# MLX90614-IR_v4.net
KiCad netlist of a schematic drawn in EAGLE
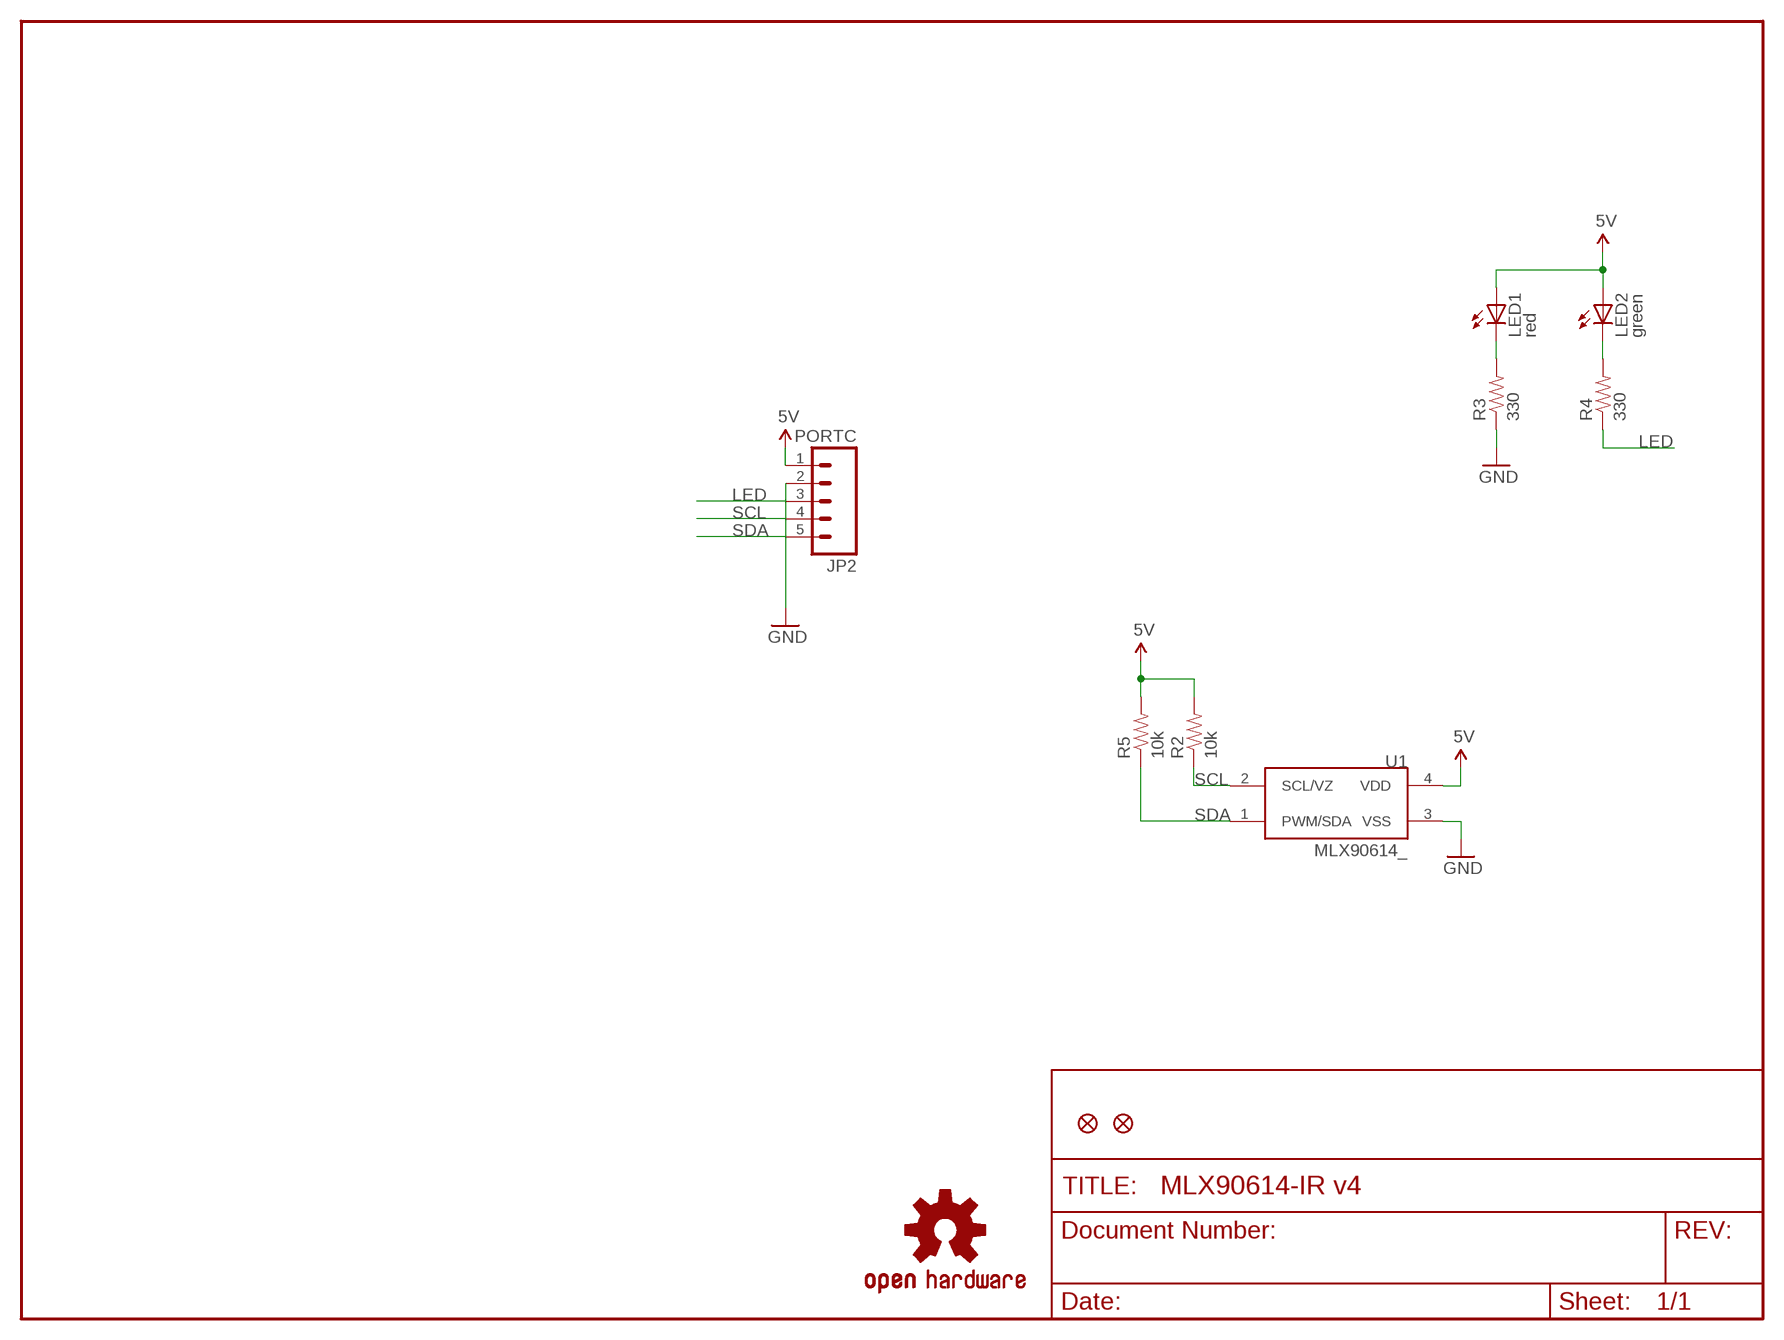
[diagram p0: schematic, sheet 1]

(export (version "E")
  (design (tool "Eeschema 10.0.6"))
  (components
    (comp (ref "JP2")
      (value "PORTC")
      (footprint "eagle-import:1X05")
      (libsource (lib "eagle-import") (part "M05PTH"))
    )
    (comp (ref "JP3")
      (value "FIDUCIAL1X2.5")
      (footprint "eagle-import:FIDUCIAL-1X2.5")
      (libsource (lib "eagle-import") (part "FIDUCIAL1X2.5"))
    )
    (comp (ref "JP5")
      (value "FIDUCIAL1X2.5")
      (footprint "eagle-import:FIDUCIAL-1X2.5")
      (libsource (lib "eagle-import") (part "FIDUCIAL1X2.5"))
    )
    (comp (ref "LED1")
      (value "red")
      (footprint "eagle-import:LED-0603")
      (libsource (lib "eagle-import") (part "LED0603"))
    )
    (comp (ref "LED2")
      (value "green")
      (footprint "eagle-import:LED-0603")
      (libsource (lib "eagle-import") (part "LED0603"))
    )
    (comp (ref "R2")
      (value "10k")
      (footprint "eagle-import:0402-RES")
      (libsource (lib "eagle-import") (part "RESISTOR0402-RES"))
    )
    (comp (ref "R3")
      (value "330")
      (footprint "eagle-import:0402-RES")
      (libsource (lib "eagle-import") (part "RESISTOR0402-RES"))
    )
    (comp (ref "R4")
      (value "330")
      (footprint "eagle-import:0402-RES")
      (libsource (lib "eagle-import") (part "RESISTOR0402-RES"))
    )
    (comp (ref "R5")
      (value "10k")
      (footprint "eagle-import:0402-RES")
      (libsource (lib "eagle-import") (part "RESISTOR0402-RES"))
    )
    (comp (ref "U$1")
      (value "OSHW-LOGOS")
      (footprint "eagle-import:OSHW-LOGO-S")
      (libsource (lib "eagle-import") (part "OSHW-LOGOS"))
    )
    (comp (ref "U1")
      (value "MLX90614_")
      (footprint "eagle-import:TO-39")
      (libsource (lib "eagle-import") (part "MLX90614_"))
    )
  )
  (nets
    (net (code "1") (name "/LED") (class "Default")
      (node (ref "JP2") (pin "3") (pinfunction "3_3") (pintype "passive"))
      (node (ref "R4") (pin "1") (pinfunction "1_1") (pintype "passive"))
    )
    (net (code "2") (name "/SCL") (class "Default")
      (node (ref "JP2") (pin "4") (pinfunction "4_4") (pintype "passive"))
      (node (ref "R2") (pin "1") (pinfunction "1_1") (pintype "passive"))
      (node (ref "U1") (pin "2") (pinfunction "SCL/VZ_2") (pintype "bidirectional"))
    )
    (net (code "3") (name "/SDA") (class "Default")
      (node (ref "JP2") (pin "5") (pinfunction "5_5") (pintype "passive"))
      (node (ref "R5") (pin "1") (pinfunction "1_1") (pintype "passive"))
      (node (ref "U1") (pin "1") (pinfunction "PWM/SDA_1") (pintype "bidirectional"))
    )
    (net (code "4") (name "5V") (class "Default")
      (node (ref "JP2") (pin "1") (pinfunction "1_1") (pintype "passive"))
      (node (ref "LED1") (pin "A") (pinfunction "A_A") (pintype "passive"))
      (node (ref "LED2") (pin "A") (pinfunction "A_A") (pintype "passive"))
      (node (ref "R2") (pin "2") (pinfunction "2_2") (pintype "passive"))
      (node (ref "R5") (pin "2") (pinfunction "2_2") (pintype "passive"))
      (node (ref "U1") (pin "4") (pinfunction "VDD_4") (pintype "bidirectional"))
    )
    (net (code "5") (name "GND") (class "Default")
      (node (ref "JP2") (pin "2") (pinfunction "2_2") (pintype "passive"))
      (node (ref "R3") (pin "1") (pinfunction "1_1") (pintype "passive"))
      (node (ref "U1") (pin "3") (pinfunction "VSS_3") (pintype "bidirectional"))
    )
    (net (code "6") (name "Net-(LED1-PadC)") (class "Default")
      (node (ref "LED1") (pin "C") (pinfunction "C_C") (pintype "passive"))
      (node (ref "R3") (pin "2") (pinfunction "2_2") (pintype "passive"))
    )
    (net (code "7") (name "Net-(LED2-PadC)") (class "Default")
      (node (ref "LED2") (pin "C") (pinfunction "C_C") (pintype "passive"))
      (node (ref "R4") (pin "2") (pinfunction "2_2") (pintype "passive"))
    )
  )
)
